# 04_CAN.net
KiCad netlist of a schematic drawn in Altium Designer
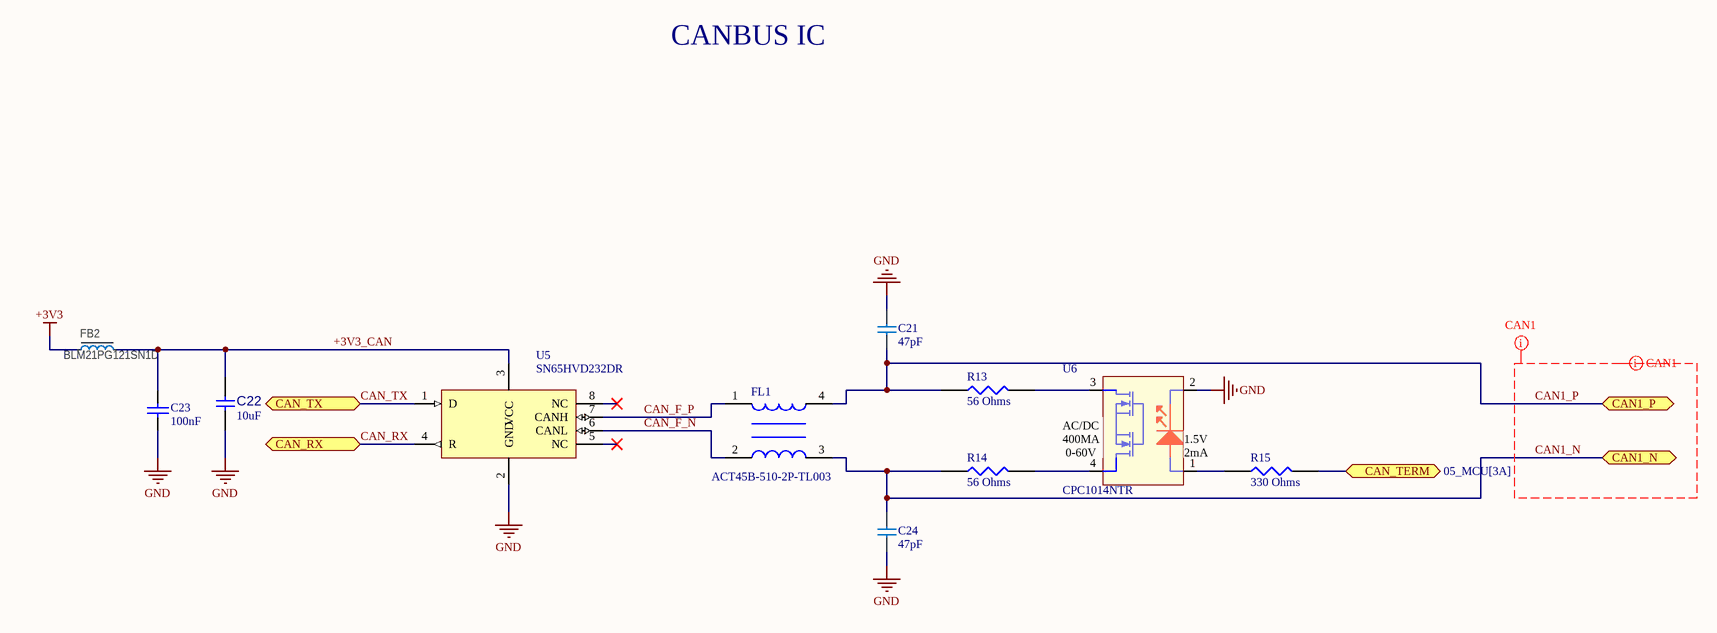
[diagram p0: 04_CAN.SchDoc]

(export (version "E")
  (design (tool "Eeschema 10.0.6"))
  (components
    (comp (ref "C21")
      (value "47pF")
      (footprint "CAPC1608X100N")
      (description "47 pF ±1% 200V Ceramic Capacitor C0G, NP0 0603 (1608 Metric)")
      (fields
        (field (name "MPN") "GMC10CG470F200NT")
        (field (name "MANUFACTURER") "Cal-Chip Electronics, Inc.")
      )
      (libsource (lib "HW_ADHERENT_NFC_R1_L1") (part "GMC10CG470F200NT"))
    )
    (comp (ref "C22")
      (value "10uF")
      (footprint "0603_C")
      (description "CAP CER 10UF 25V X5R 0603")
      (fields (field (name "VOLTAGE") "25V") (field (name "MANUFACTURER") "Murata Electronics North America"))
      (libsource (lib "HW_ADHERENT_NFC_R1_L3") (part "CAP1461"))
    )
    (comp (ref "C23")
      (value "100nF")
      (footprint "CAP0603")
      (description "CAP CER 0.1UF 50V X7R 0603")
      (libsource (lib "CAP_Library") (part "CAP0603_100nF"))
    )
    (comp (ref "C24")
      (value "47pF")
      (footprint "CAPC1608X100N")
      (description "47 pF ±1% 200V Ceramic Capacitor C0G, NP0 0603 (1608 Metric)")
      (fields
        (field (name "MPN") "GMC10CG470F200NT")
        (field (name "MANUFACTURER") "Cal-Chip Electronics, Inc.")
      )
      (libsource (lib "HW_ADHERENT_NFC_R1_L1") (part "GMC10CG470F200NT"))
    )
    (comp (ref "FB2")
      (value "BLM21PG121SN1D")
      (footprint "INDC2012X11L")
      (description "Ferrite Bead, 120 Ohm @ 100MHz, 500mA, 250 mOhm Max")
      (fields
        (field (name "PART NUMBER") "FB0402-120R@100M-500mA")
        (field (name "MANUFACTURER") "Murata")
        (field (name "AUTHOR") "rsk")
      )
      (libsource (lib "HW_PEINFO_CRANECTRL_KEY20_R1") (part "FB0402-120R@100M-500mA"))
    )
    (comp (ref "FL1")
      (value "ACT45B-510-2P-TL003")
      (footprint "FIL_ACT45B-510-2P-TL003")
      (description "51 ÂµH @ 100 kHz 2 Line Common Mode Choke Surface Mount 2.8 kOhms @ 10 MHz 200mA DCR 1Ohm")
      (fields (field (name "MF") "TDK"))
      (libsource (lib "HW_PEINFO_CRANECTRL_KEY20_R1") (part "ACT45B-510-2P-TL003"))
    )
    (comp (ref "R13")
      (value "56 Ohms")
      (footprint "RES_0402")
      (description "56 Ohms ±1% 0.063W, 1/16W Chip Resistor 0402 (1005 Metric) Automotive AEC-Q200 Thick Film")
      (libsource (lib "HW_ADHERENT_NFC_R1_L1") (part "RMCF0402FT56R0"))
    )
    (comp (ref "R14")
      (value "56 Ohms")
      (footprint "RES_0402")
      (description "56 Ohms ±1% 0.063W, 1/16W Chip Resistor 0402 (1005 Metric) Automotive AEC-Q200 Thick Film")
      (libsource (lib "HW_ADHERENT_NFC_R1_L1") (part "RMCF0402FT56R0"))
    )
    (comp (ref "R15")
      (value "330 Ohms")
      (footprint "RES_0402")
      (description "330 Ohms ±1% 0.063W, 1/16W Chip Resistor 0402 (1005 Metric) Automotive AEC-Q200 Thick Film")
      (libsource (lib "HW_ADHERENT_NFC_R1_L1") (part "RMCF0402FT330R"))
    )
    (comp (ref "U5")
      (value "SN65HVD232DR")
      (footprint "SOIC8")
      (description "1Mbps Transceiver 3V~3.6V SOIC-8 CAN ICs ROHS")
      (fields (field (name "LCSC PART NUMBER") "C30530"))
      (libsource (lib "HW_PEINFO_RF_RECEIVER_R1") (part "SN65HVD232DR"))
    )
    (comp (ref "U6")
      (value "CPC1014NTR")
      (footprint "4-SOP")
      (description "SSR RELAY SPST-NO 400MA 0-60V")
      (fields (field (name "MANUFACTURER") "IXYS Integrated Circuits Division"))
      (libsource (lib "HW_ADHERENT_NFC_R1_L2") (part "CPC1014NTR"))
    )
  )
  (nets
    (net (code "1") (name "+3V3") (class "Default")
      (node (ref "FB2") (pin "1") (pinfunction "1_1") (pintype "passive"))
    )
    (net (code "2") (name "/+3V3_CAN") (class "Default")
      (node (ref "C22") (pin "2") (pinfunction "2_2") (pintype "passive"))
      (node (ref "C23") (pin "1") (pinfunction "1_1") (pintype "passive"))
      (node (ref "FB2") (pin "2") (pinfunction "2_2") (pintype "passive"))
      (node (ref "U5") (pin "3") (pinfunction "VCC_3") (pintype "power_in"))
    )
    (net (code "3") (name "/CAN1_N") (class "Default")
      (node (ref "C24") (pin "2") (pinfunction "2_2") (pintype "passive"))
      (node (ref "FL1") (pin "3") (pinfunction "3_3") (pintype "passive"))
      (node (ref "R14") (pin "1") (pinfunction "1_1") (pintype "passive"))
    )
    (net (code "4") (name "/CAN1_P") (class "Default")
      (node (ref "C21") (pin "1") (pinfunction "1_1") (pintype "passive"))
      (node (ref "FL1") (pin "4") (pinfunction "4_4") (pintype "passive"))
      (node (ref "R13") (pin "1") (pinfunction "1_1") (pintype "passive"))
    )
    (net (code "5") (name "/CAN_F_N") (class "Default")
      (node (ref "FL1") (pin "2") (pinfunction "2_2") (pintype "passive"))
      (node (ref "U5") (pin "6") (pinfunction "CANL_6") (pintype "bidirectional"))
    )
    (net (code "6") (name "/CAN_F_P") (class "Default")
      (node (ref "FL1") (pin "1") (pinfunction "1_1") (pintype "passive"))
      (node (ref "U5") (pin "7") (pinfunction "CANH_7") (pintype "bidirectional"))
    )
    (net (code "7") (name "/CAN_RX") (class "Default")
      (node (ref "U5") (pin "4") (pinfunction "R_4") (pintype "output"))
    )
    (net (code "8") (name "/CAN_TERM") (class "Default")
      (node (ref "R15") (pin "2") (pinfunction "2_2") (pintype "passive"))
    )
    (net (code "9") (name "/CAN_TX") (class "Default")
      (node (ref "U5") (pin "1") (pinfunction "D_1") (pintype "input"))
    )
    (net (code "10") (name "GND") (class "Default")
      (node (ref "C21") (pin "2") (pinfunction "2_2") (pintype "passive"))
      (node (ref "C22") (pin "1") (pinfunction "1_1") (pintype "passive"))
      (node (ref "C23") (pin "2") (pinfunction "2_2") (pintype "passive"))
      (node (ref "C24") (pin "1") (pinfunction "1_1") (pintype "passive"))
      (node (ref "U5") (pin "2") (pinfunction "GND_2") (pintype "power_in"))
      (node (ref "U6") (pin "2") (pinfunction "CATHODE1_2") (pintype "passive"))
    )
    (net (code "11") (name "Net-(R13-Pad2)") (class "Default")
      (node (ref "R13") (pin "2") (pinfunction "2_2") (pintype "passive"))
      (node (ref "U6") (pin "3") (pinfunction "3_3") (pintype "passive"))
    )
    (net (code "12") (name "Net-(R14-Pad2)") (class "Default")
      (node (ref "R14") (pin "2") (pinfunction "2_2") (pintype "passive"))
      (node (ref "U6") (pin "4") (pinfunction "4_4") (pintype "passive"))
    )
    (net (code "13") (name "Net-(U6-ANODE)") (class "Default")
      (node (ref "R15") (pin "1") (pinfunction "1_1") (pintype "passive"))
      (node (ref "U6") (pin "1") (pinfunction "ANODE_1") (pintype "passive"))
    )
    (net (code "14") (name "unconnected-(U5-NC-Pad5)") (class "Default")
      (node (ref "U5") (pin "5") (pinfunction "NC_5") (pintype "passive+no_connect"))
    )
    (net (code "15") (name "unconnected-(U5-NC-Pad8)") (class "Default")
      (node (ref "U5") (pin "8") (pinfunction "NC_8") (pintype "passive+no_connect"))
    )
  )
)
